# Yahoo5NewsViewWtithWeather.net
KiCad netlist of a schematic drawn in EAGLE
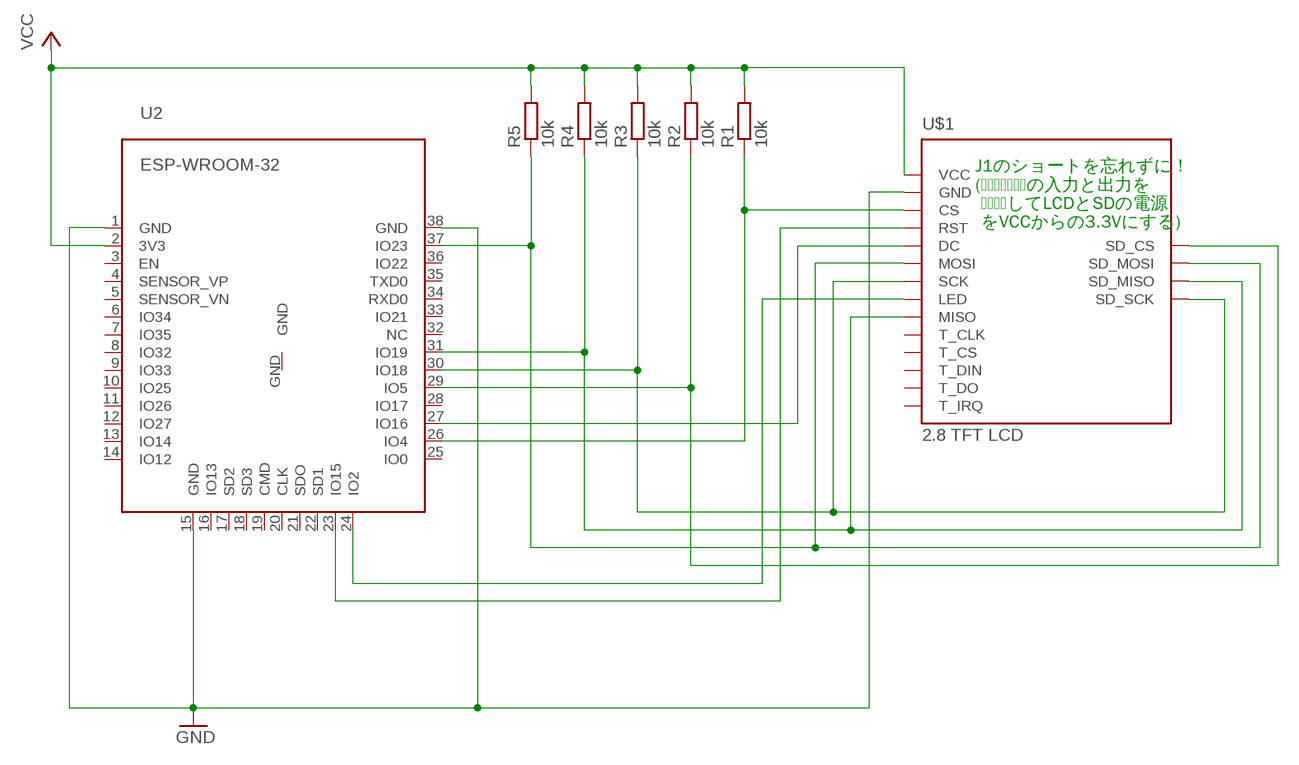
[diagram p0: schematic, sheet 1]

(export (version "E")
  (design (tool "Eeschema 10.0.6"))
  (components
    (comp (ref "R1")
      (value "10k")
      (footprint "eagle-import:0204_5")
      (libsource (lib "eagle-import") (part "R-EU_0204/5"))
    )
    (comp (ref "R2")
      (value "10k")
      (footprint "eagle-import:0204_5")
      (libsource (lib "eagle-import") (part "R-EU_0204/5"))
    )
    (comp (ref "R3")
      (value "10k")
      (footprint "eagle-import:0204_5")
      (libsource (lib "eagle-import") (part "R-EU_0204/5"))
    )
    (comp (ref "R4")
      (value "10k")
      (footprint "eagle-import:0204_5")
      (libsource (lib "eagle-import") (part "R-EU_0204/5"))
    )
    (comp (ref "R5")
      (value "10k")
      (footprint "eagle-import:0204_5")
      (libsource (lib "eagle-import") (part "R-EU_0204/5"))
    )
    (comp (ref "U$1")
      (value "2.8_TFT_LCD")
      (footprint "eagle-import:2.8_TFT_LCD")
      (libsource (lib "eagle-import") (part "2.8_TFT_LCD"))
    )
    (comp (ref "U2")
      (value "ESP-WROOM-32")
      (footprint "eagle-import:ESP-WROOM-32")
      (libsource (lib "eagle-import") (part "ESP-WROOM-32"))
    )
  )
  (nets
    (net (code "1") (name "GND") (class "Default")
      (node (ref "U$1") (pin "GND") (pinfunction "GND_GND") (pintype "power_in"))
      (node (ref "U2") (pin "1") (pinfunction "GND_1") (pintype "bidirectional"))
      (node (ref "U2") (pin "15") (pinfunction "GND_15") (pintype "bidirectional"))
      (node (ref "U2") (pin "38") (pinfunction "GND_38") (pintype "bidirectional"))
    )
    (net (code "2") (name "Net-(U2-IO2)") (class "Default")
      (node (ref "U$1") (pin "LED") (pinfunction "LED_LED") (pintype "bidirectional"))
      (node (ref "U2") (pin "24") (pinfunction "IO2_24") (pintype "bidirectional"))
    )
    (net (code "3") (name "Net-(U2-IO4)") (class "Default")
      (node (ref "R1") (pin "1") (pinfunction "1_1") (pintype "passive"))
      (node (ref "U$1") (pin "CS") (pinfunction "CS_CS") (pintype "bidirectional"))
      (node (ref "U2") (pin "26") (pinfunction "IO4_26") (pintype "bidirectional"))
    )
    (net (code "4") (name "Net-(U2-IO5)") (class "Default")
      (node (ref "R2") (pin "1") (pinfunction "1_1") (pintype "passive"))
      (node (ref "U$1") (pin "SD_CS") (pinfunction "SD_CS_SD_CS") (pintype "bidirectional"))
      (node (ref "U2") (pin "29") (pinfunction "IO5_29") (pintype "bidirectional"))
    )
    (net (code "5") (name "Net-(U2-IO15)") (class "Default")
      (node (ref "U$1") (pin "RST") (pinfunction "RST_RST") (pintype "bidirectional"))
      (node (ref "U2") (pin "23") (pinfunction "IO15_23") (pintype "bidirectional"))
    )
    (net (code "6") (name "Net-(U2-IO16)") (class "Default")
      (node (ref "U$1") (pin "DC") (pinfunction "DC_DC") (pintype "bidirectional"))
      (node (ref "U2") (pin "27") (pinfunction "IO16_27") (pintype "bidirectional"))
    )
    (net (code "7") (name "Net-(U2-IO18)") (class "Default")
      (node (ref "R3") (pin "1") (pinfunction "1_1") (pintype "passive"))
      (node (ref "U$1") (pin "SCK") (pinfunction "SCK_SCK") (pintype "bidirectional"))
      (node (ref "U$1") (pin "SD_SCK") (pinfunction "SD_SCK_SD_SCK") (pintype "bidirectional"))
      (node (ref "U2") (pin "30") (pinfunction "IO18_30") (pintype "bidirectional"))
    )
    (net (code "8") (name "Net-(U2-IO19)") (class "Default")
      (node (ref "R4") (pin "1") (pinfunction "1_1") (pintype "passive"))
      (node (ref "U$1") (pin "MISO") (pinfunction "MISO_MISO") (pintype "bidirectional"))
      (node (ref "U$1") (pin "SD_MISO") (pinfunction "SD_MISO_SD_MISO") (pintype "bidirectional"))
      (node (ref "U2") (pin "31") (pinfunction "IO19_31") (pintype "bidirectional"))
    )
    (net (code "9") (name "Net-(U2-IO23)") (class "Default")
      (node (ref "R5") (pin "1") (pinfunction "1_1") (pintype "passive"))
      (node (ref "U$1") (pin "MOSI") (pinfunction "MOSI_MOSI") (pintype "bidirectional"))
      (node (ref "U$1") (pin "SD_MOSI") (pinfunction "SD_MOSI_SD_MOSI") (pintype "bidirectional"))
      (node (ref "U2") (pin "37") (pinfunction "IO23_37") (pintype "bidirectional"))
    )
    (net (code "10") (name "VCC") (class "Default")
      (node (ref "R1") (pin "2") (pinfunction "2_2") (pintype "passive"))
      (node (ref "R2") (pin "2") (pinfunction "2_2") (pintype "passive"))
      (node (ref "R3") (pin "2") (pinfunction "2_2") (pintype "passive"))
      (node (ref "R4") (pin "2") (pinfunction "2_2") (pintype "passive"))
      (node (ref "R5") (pin "2") (pinfunction "2_2") (pintype "passive"))
      (node (ref "U$1") (pin "VCC") (pinfunction "VCC_VCC") (pintype "power_in"))
      (node (ref "U2") (pin "2") (pinfunction "3V3_2") (pintype "bidirectional"))
    )
    (net (code "11") (name "unconnected-(U$1-PadT_CLK)") (class "Default")
      (node (ref "U$1") (pin "T_CLK") (pinfunction "T_CLK_T_CLK") (pintype "bidirectional"))
    )
    (net (code "12") (name "unconnected-(U$1-PadT_CS)") (class "Default")
      (node (ref "U$1") (pin "T_CS") (pinfunction "T_CS_T_CS") (pintype "bidirectional"))
    )
    (net (code "13") (name "unconnected-(U$1-PadT_DIN)") (class "Default")
      (node (ref "U$1") (pin "T_DIN") (pinfunction "T_DIN_T_DIN") (pintype "bidirectional"))
    )
    (net (code "14") (name "unconnected-(U$1-PadT_DO)") (class "Default")
      (node (ref "U$1") (pin "T_DO") (pinfunction "T_DO_T_DO") (pintype "bidirectional"))
    )
    (net (code "15") (name "unconnected-(U$1-PadT_IRQ)") (class "Default")
      (node (ref "U$1") (pin "T_IRQ") (pinfunction "T_IRQ_T_IRQ") (pintype "bidirectional"))
    )
    (net (code "16") (name "unconnected-(U2-CLK-Pad20)") (class "Default")
      (node (ref "U2") (pin "20") (pinfunction "CLK_20") (pintype "bidirectional"))
    )
    (net (code "17") (name "unconnected-(U2-CMD-Pad19)") (class "Default")
      (node (ref "U2") (pin "19") (pinfunction "CMD_19") (pintype "bidirectional"))
    )
    (net (code "18") (name "unconnected-(U2-EN-Pad3)") (class "Default")
      (node (ref "U2") (pin "3") (pinfunction "EN_3") (pintype "bidirectional"))
    )
    (net (code "19") (name "unconnected-(U2-IO0-Pad25)") (class "Default")
      (node (ref "U2") (pin "25") (pinfunction "IO0_25") (pintype "bidirectional"))
    )
    (net (code "20") (name "unconnected-(U2-IO12-Pad14)") (class "Default")
      (node (ref "U2") (pin "14") (pinfunction "IO12_14") (pintype "bidirectional"))
    )
    (net (code "21") (name "unconnected-(U2-IO13-Pad16)") (class "Default")
      (node (ref "U2") (pin "16") (pinfunction "IO13_16") (pintype "bidirectional"))
    )
    (net (code "22") (name "unconnected-(U2-IO14-Pad13)") (class "Default")
      (node (ref "U2") (pin "13") (pinfunction "IO14_13") (pintype "bidirectional"))
    )
    (net (code "23") (name "unconnected-(U2-IO17-Pad28)") (class "Default")
      (node (ref "U2") (pin "28") (pinfunction "IO17_28") (pintype "bidirectional"))
    )
    (net (code "24") (name "unconnected-(U2-IO21-Pad33)") (class "Default")
      (node (ref "U2") (pin "33") (pinfunction "IO21_33") (pintype "bidirectional"))
    )
    (net (code "25") (name "unconnected-(U2-IO22-Pad36)") (class "Default")
      (node (ref "U2") (pin "36") (pinfunction "IO22_36") (pintype "bidirectional"))
    )
    (net (code "26") (name "unconnected-(U2-IO25-Pad10)") (class "Default")
      (node (ref "U2") (pin "10") (pinfunction "IO25_10") (pintype "bidirectional"))
    )
    (net (code "27") (name "unconnected-(U2-IO26-Pad11)") (class "Default")
      (node (ref "U2") (pin "11") (pinfunction "IO26_11") (pintype "bidirectional"))
    )
    (net (code "28") (name "unconnected-(U2-IO27-Pad12)") (class "Default")
      (node (ref "U2") (pin "12") (pinfunction "IO27_12") (pintype "bidirectional"))
    )
    (net (code "29") (name "unconnected-(U2-IO32-Pad8)") (class "Default")
      (node (ref "U2") (pin "8") (pinfunction "IO32_8") (pintype "bidirectional"))
    )
    (net (code "30") (name "unconnected-(U2-IO33-Pad9)") (class "Default")
      (node (ref "U2") (pin "9") (pinfunction "IO33_9") (pintype "bidirectional"))
    )
    (net (code "31") (name "unconnected-(U2-IO34-Pad6)") (class "Default")
      (node (ref "U2") (pin "6") (pinfunction "IO34_6") (pintype "bidirectional"))
    )
    (net (code "32") (name "unconnected-(U2-IO35-Pad7)") (class "Default")
      (node (ref "U2") (pin "7") (pinfunction "IO35_7") (pintype "bidirectional"))
    )
    (net (code "33") (name "unconnected-(U2-NC-Pad32)") (class "Default")
      (node (ref "U2") (pin "32") (pinfunction "NC_32") (pintype "bidirectional"))
    )
    (net (code "34") (name "unconnected-(U2-PadGND)") (class "Default")
      (node (ref "U2") (pin "GND") (pinfunction "GND_GND") (pintype "bidirectional"))
    )
    (net (code "35") (name "unconnected-(U2-RXD0-Pad34)") (class "Default")
      (node (ref "U2") (pin "34") (pinfunction "RXD0_34") (pintype "bidirectional"))
    )
    (net (code "36") (name "unconnected-(U2-SD1-Pad22)") (class "Default")
      (node (ref "U2") (pin "22") (pinfunction "SD1_22") (pintype "bidirectional"))
    )
    (net (code "37") (name "unconnected-(U2-SD2-Pad17)") (class "Default")
      (node (ref "U2") (pin "17") (pinfunction "SD2_17") (pintype "bidirectional"))
    )
    (net (code "38") (name "unconnected-(U2-SD3-Pad18)") (class "Default")
      (node (ref "U2") (pin "18") (pinfunction "SD3_18") (pintype "bidirectional"))
    )
    (net (code "39") (name "unconnected-(U2-SDO-Pad21)") (class "Default")
      (node (ref "U2") (pin "21") (pinfunction "SDO_21") (pintype "bidirectional"))
    )
    (net (code "40") (name "unconnected-(U2-SENSOR_VN-Pad5)") (class "Default")
      (node (ref "U2") (pin "5") (pinfunction "SENSOR_VN_5") (pintype "bidirectional"))
    )
    (net (code "41") (name "unconnected-(U2-SENSOR_VP-Pad4)") (class "Default")
      (node (ref "U2") (pin "4") (pinfunction "SENSOR_VP_4") (pintype "bidirectional"))
    )
    (net (code "42") (name "unconnected-(U2-TXD0-Pad35)") (class "Default")
      (node (ref "U2") (pin "35") (pinfunction "TXD0_35") (pintype "bidirectional"))
    )
  )
)
